# Sheet1.net
KiCad netlist of a schematic drawn in Altium Designer
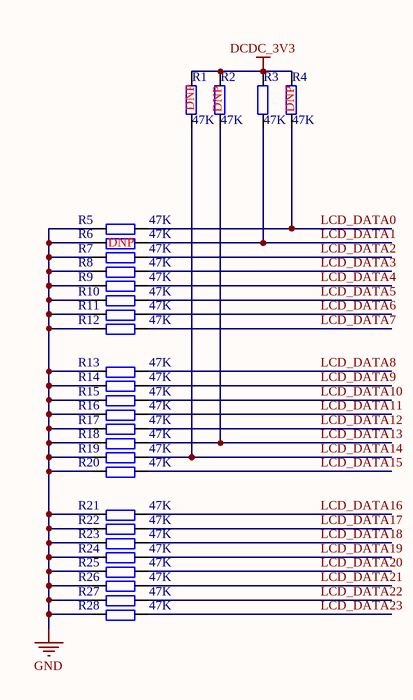
[diagram p0: Sheet1.SchDoc]

(export (version "E")
  (design (tool "Eeschema 10.0.6"))
  (components
    (comp (ref "R1") (value "47K") (footprint "R 0402") (libsource (lib "IMX6ULL_CORE(核心板)_V1.4") (part "R")))
    (comp (ref "R2") (value "47K") (footprint "R 0402") (libsource (lib "IMX6ULL_CORE(核心板)_V1.4") (part "R")))
    (comp (ref "R3") (value "47K") (footprint "R 0402") (libsource (lib "IMX6ULL_CORE(核心板)_V1.4") (part "R")))
    (comp (ref "R4") (value "47K") (footprint "R 0402") (libsource (lib "IMX6ULL_CORE(核心板)_V1.4") (part "R")))
    (comp (ref "R5") (value "47K") (footprint "R 0402") (libsource (lib "IMX6ULL_CORE(核心板)_V1.4") (part "R")))
    (comp (ref "R6") (value "47K") (footprint "R 0402") (libsource (lib "IMX6ULL_CORE(核心板)_V1.4") (part "R")))
    (comp (ref "R7") (value "47K") (footprint "R 0402") (libsource (lib "IMX6ULL_CORE(核心板)_V1.4") (part "R")))
    (comp (ref "R8") (value "47K") (footprint "R 0402") (libsource (lib "IMX6ULL_CORE(核心板)_V1.4") (part "R")))
    (comp (ref "R9") (value "47K") (footprint "R 0402") (libsource (lib "IMX6ULL_CORE(核心板)_V1.4") (part "R")))
    (comp (ref "R10")
      (value "47K")
      (footprint "R 0402")
      (libsource (lib "IMX6ULL_CORE(核心板)_V1.4") (part "R"))
    )
    (comp (ref "R11")
      (value "47K")
      (footprint "R 0402")
      (libsource (lib "IMX6ULL_CORE(核心板)_V1.4") (part "R"))
    )
    (comp (ref "R12")
      (value "47K")
      (footprint "R 0402")
      (libsource (lib "IMX6ULL_CORE(核心板)_V1.4") (part "R"))
    )
    (comp (ref "R13")
      (value "47K")
      (footprint "R 0402")
      (libsource (lib "IMX6ULL_CORE(核心板)_V1.4") (part "R"))
    )
    (comp (ref "R14")
      (value "47K")
      (footprint "R 0402")
      (libsource (lib "IMX6ULL_CORE(核心板)_V1.4") (part "R"))
    )
    (comp (ref "R15")
      (value "47K")
      (footprint "R 0402")
      (libsource (lib "IMX6ULL_CORE(核心板)_V1.4") (part "R"))
    )
    (comp (ref "R16")
      (value "47K")
      (footprint "R 0402")
      (libsource (lib "IMX6ULL_CORE(核心板)_V1.4") (part "R"))
    )
    (comp (ref "R17")
      (value "47K")
      (footprint "R 0402")
      (libsource (lib "IMX6ULL_CORE(核心板)_V1.4") (part "R"))
    )
    (comp (ref "R18")
      (value "47K")
      (footprint "R 0402")
      (libsource (lib "IMX6ULL_CORE(核心板)_V1.4") (part "R"))
    )
    (comp (ref "R19")
      (value "47K")
      (footprint "R 0402")
      (libsource (lib "IMX6ULL_CORE(核心板)_V1.4") (part "R"))
    )
    (comp (ref "R20")
      (value "47K")
      (footprint "R 0402")
      (libsource (lib "IMX6ULL_CORE(核心板)_V1.4") (part "R"))
    )
    (comp (ref "R21")
      (value "47K")
      (footprint "R 0402")
      (libsource (lib "IMX6ULL_CORE(核心板)_V1.4") (part "R"))
    )
    (comp (ref "R22")
      (value "47K")
      (footprint "R 0402")
      (libsource (lib "IMX6ULL_CORE(核心板)_V1.4") (part "R"))
    )
    (comp (ref "R23")
      (value "47K")
      (footprint "R 0402")
      (libsource (lib "IMX6ULL_CORE(核心板)_V1.4") (part "R"))
    )
    (comp (ref "R24")
      (value "47K")
      (footprint "R 0402")
      (libsource (lib "IMX6ULL_CORE(核心板)_V1.4") (part "R"))
    )
    (comp (ref "R25")
      (value "47K")
      (footprint "R 0402")
      (libsource (lib "IMX6ULL_CORE(核心板)_V1.4") (part "R"))
    )
    (comp (ref "R26")
      (value "47K")
      (footprint "R 0402")
      (libsource (lib "IMX6ULL_CORE(核心板)_V1.4") (part "R"))
    )
    (comp (ref "R27")
      (value "47K")
      (footprint "R 0402")
      (libsource (lib "IMX6ULL_CORE(核心板)_V1.4") (part "R"))
    )
    (comp (ref "R28")
      (value "47K")
      (footprint "R 0402")
      (libsource (lib "IMX6ULL_CORE(核心板)_V1.4") (part "R"))
    )
  )
  (nets
    (net (code "1") (name "/LCD_DATA0") (class "Default")
      (node (ref "R4") (pin "2") (pintype "passive"))
      (node (ref "R5") (pin "2") (pintype "passive"))
    )
    (net (code "2") (name "/LCD_DATA1") (class "Default")
      (node (ref "R3") (pin "2") (pintype "passive"))
      (node (ref "R6") (pin "2") (pintype "passive"))
    )
    (net (code "3") (name "/LCD_DATA2") (class "Default") (node (ref "R7") (pin "2") (pintype "passive")))
    (net (code "4") (name "/LCD_DATA3") (class "Default") (node (ref "R8") (pin "2") (pintype "passive")))
    (net (code "5") (name "/LCD_DATA4") (class "Default") (node (ref "R9") (pin "2") (pintype "passive")))
    (net (code "6") (name "/LCD_DATA5") (class "Default") (node (ref "R10") (pin "2") (pintype "passive")))
    (net (code "7") (name "/LCD_DATA6") (class "Default") (node (ref "R11") (pin "2") (pintype "passive")))
    (net (code "8") (name "/LCD_DATA7") (class "Default") (node (ref "R12") (pin "2") (pintype "passive")))
    (net (code "9") (name "/LCD_DATA8") (class "Default") (node (ref "R13") (pin "2") (pintype "passive")))
    (net (code "10") (name "/LCD_DATA9") (class "Default") (node (ref "R14") (pin "2") (pintype "passive")))
    (net (code "11") (name "/LCD_DATA10") (class "Default") (node (ref "R15") (pin "2") (pintype "passive")))
    (net (code "12") (name "/LCD_DATA11") (class "Default") (node (ref "R16") (pin "2") (pintype "passive")))
    (net (code "13") (name "/LCD_DATA12") (class "Default") (node (ref "R17") (pin "2") (pintype "passive")))
    (net (code "14") (name "/LCD_DATA13") (class "Default")
      (node (ref "R18") (pin "2") (pintype "passive"))
      (node (ref "R2") (pin "2") (pintype "passive"))
    )
    (net (code "15") (name "/LCD_DATA14") (class "Default")
      (node (ref "R1") (pin "2") (pintype "passive"))
      (node (ref "R19") (pin "2") (pintype "passive"))
    )
    (net (code "16") (name "/LCD_DATA15") (class "Default") (node (ref "R20") (pin "2") (pintype "passive")))
    (net (code "17") (name "/LCD_DATA16") (class "Default") (node (ref "R21") (pin "2") (pintype "passive")))
    (net (code "18") (name "/LCD_DATA17") (class "Default") (node (ref "R22") (pin "2") (pintype "passive")))
    (net (code "19") (name "/LCD_DATA18") (class "Default") (node (ref "R23") (pin "2") (pintype "passive")))
    (net (code "20") (name "/LCD_DATA19") (class "Default") (node (ref "R24") (pin "2") (pintype "passive")))
    (net (code "21") (name "/LCD_DATA20") (class "Default") (node (ref "R25") (pin "2") (pintype "passive")))
    (net (code "22") (name "/LCD_DATA21") (class "Default") (node (ref "R26") (pin "2") (pintype "passive")))
    (net (code "23") (name "/LCD_DATA22") (class "Default") (node (ref "R27") (pin "2") (pintype "passive")))
    (net (code "24") (name "/LCD_DATA23") (class "Default") (node (ref "R28") (pin "2") (pintype "passive")))
    (net (code "25") (name "DCDC_3V3") (class "Default")
      (node (ref "R1") (pin "1") (pintype "passive"))
      (node (ref "R2") (pin "1") (pintype "passive"))
      (node (ref "R3") (pin "1") (pintype "passive"))
      (node (ref "R4") (pin "1") (pintype "passive"))
    )
    (net (code "26") (name "GND") (class "Default")
      (node (ref "R10") (pin "1") (pintype "passive"))
      (node (ref "R11") (pin "1") (pintype "passive"))
      (node (ref "R12") (pin "1") (pintype "passive"))
      (node (ref "R13") (pin "1") (pintype "passive"))
      (node (ref "R14") (pin "1") (pintype "passive"))
      (node (ref "R15") (pin "1") (pintype "passive"))
      (node (ref "R16") (pin "1") (pintype "passive"))
      (node (ref "R17") (pin "1") (pintype "passive"))
      (node (ref "R18") (pin "1") (pintype "passive"))
      (node (ref "R19") (pin "1") (pintype "passive"))
      (node (ref "R20") (pin "1") (pintype "passive"))
      (node (ref "R21") (pin "1") (pintype "passive"))
      (node (ref "R22") (pin "1") (pintype "passive"))
      (node (ref "R23") (pin "1") (pintype "passive"))
      (node (ref "R24") (pin "1") (pintype "passive"))
      (node (ref "R25") (pin "1") (pintype "passive"))
      (node (ref "R26") (pin "1") (pintype "passive"))
      (node (ref "R27") (pin "1") (pintype "passive"))
      (node (ref "R28") (pin "1") (pintype "passive"))
      (node (ref "R5") (pin "1") (pintype "passive"))
      (node (ref "R6") (pin "1") (pintype "passive"))
      (node (ref "R7") (pin "1") (pintype "passive"))
      (node (ref "R8") (pin "1") (pintype "passive"))
      (node (ref "R9") (pin "1") (pintype "passive"))
    )
  )
)
